# bluetooth_2.net
KiCad netlist of a schematic drawn in Altium Designer
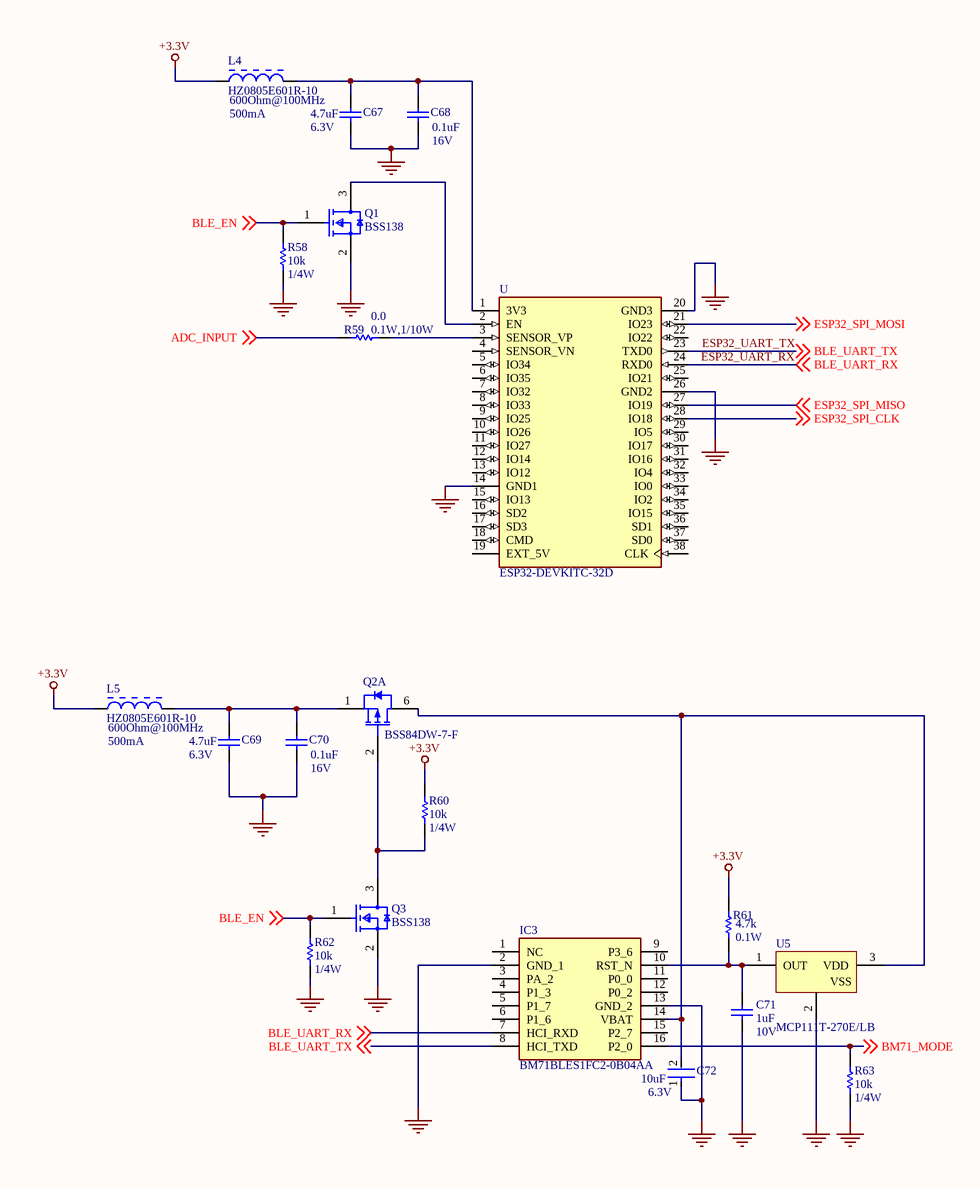
[diagram p0: bluetooth 2.SchDoc]

(export (version "E")
  (design (tool "Eeschema 10.0.6"))
  (components
    (comp (ref "C67")
      (value "4.7uF")
      (footprint "CAPC2013X145X50NL20T25")
      (fields
        (field (name "PART NUMBER") "C0805C475K9PACTU")
        (field (name "MANUFACTURER") "Kemet")
        (field (name "VOLTAGE") "6.3V")
      )
      (libsource (lib "Altium Content Vault") (part "CAP"))
    )
    (comp (ref "C68")
      (value "0.1uF")
      (footprint "CAPC1608X87X35ML15T15")
      (description "Ceramic Capacitor 0.1uF 16V +-10% X7R0603")
      (fields
        (field (name "PART NUMBER") "C0603C104M4RACTU")
        (field (name "MANUFACTURER") "Kemet")
        (field (name "VOLTAGE") "16V")
      )
      (libsource (lib "Altium Content Vault") (part "CAP"))
    )
    (comp (ref "C69")
      (value "4.7uF")
      (footprint "CAPC2013X145X50NL20T25")
      (fields
        (field (name "PART NUMBER") "C0805C475K9PACTU")
        (field (name "MANUFACTURER") "Kemet")
        (field (name "VOLTAGE") "6.3V")
      )
      (libsource (lib "Altium Content Vault") (part "CAP"))
    )
    (comp (ref "C70")
      (value "0.1uF")
      (footprint "CAPC1608X87X35ML15T15")
      (description "Ceramic Capacitor 0.1uF 16V +-10% X7R0603")
      (fields
        (field (name "PART NUMBER") "C0603C104M4RACTU")
        (field (name "MANUFACTURER") "Kemet")
        (field (name "VOLTAGE") "16V")
      )
      (libsource (lib "Altium Content Vault") (part "CAP"))
    )
    (comp (ref "C71")
      (value "1uF")
      (footprint "CAPC1608X90X35ML15T15")
      (fields
        (field (name "MANUFACTURER") "Kemet")
        (field (name "PART NUMBER") "C0603C105K8RACTU")
        (field (name "VOLTAGE") "10V")
      )
      (libsource (lib "Altium Content Vault") (part "CAP"))
    )
    (comp (ref "C72")
      (value "10uF")
      (footprint "FP-CL10-IPC_C")
      (description "Cap Ceramic 10uF 6.3V X5R ±20% Pad SMD 0603 +85°C T/R")
      (fields
        (field (name "VOLTAGE") "6.3V")
        (field (name "TOLERANCE") "20%")
        (field (name "MANUFACTURER") "Samsung")
      )
      (libsource (lib "Altium Content Vault") (part "b4654b650e69147ec39a6b967a45e02"))
    )
    (comp (ref "IC3")
      (value "BM71BLES1FC2-0B04AA")
      (footprint "SamacSys:BM71BLES1FC2_1")
      (description "Integrated Circuit")
      (fields (field (name "MOUSER PART NUMBER") "579-BM71BS1FC2-BB04"))
      (libsource (lib "SamacSys") (part "BM71BLES1FC2-0B04AA"))
    )
    (comp (ref "L4")
      (value "HZ0805E601R-10")
      (footprint "LIRD-LI0805H151R-10-2_V")
      (fields
        (field (name "IMPEDANCE @ FREQUENCY") "600Ohm@100MHz")
        (field (name "MANUFACTURER") "Laird")
        (field (name "CURRENT RATING (MAX)") "500mA")
      )
      (libsource (lib "Altium Content Vault") (part "IND-FB-2"))
    )
    (comp (ref "L5")
      (value "HZ0805E601R-10")
      (footprint "LIRD-LI0805H151R-10-2_V")
      (fields
        (field (name "IMPEDANCE @ FREQUENCY") "600Ohm@100MHz")
        (field (name "MANUFACTURER") "Laird")
        (field (name "CURRENT RATING (MAX)") "500mA")
      )
      (libsource (lib "Altium Content Vault") (part "IND-FB-2"))
    )
    (comp (ref "Q1")
      (value "BSS138")
      (footprint "FP-318-08-IPC_B")
      (description "MOSFET N-CH 50V 220MA SOT-23")
      (libsource (lib "Altium Content Vault") (part "3b9c635fedb024a5347a57b145af9cc"))
    )
    (comp (ref "Q2")
      (value "BSS84DW-7-F")
      (footprint "DIOD-SOT363-6_V")
      (description "Dual P-Channel Enhancement Mode MOSFET, 50 VDS, -55 to 150 degC, 6-Pin SOT363, RoHS, Tape and Reel")
      (fields (field (name "MANUFACTURER") "DiodesIncorporated"))
      (libsource (lib "Altium Content Vault") (part "PEMOS-SGD-SGD-6"))
    )
    (comp (ref "Q3")
      (value "BSS138")
      (footprint "FP-318-08-IPC_B")
      (description "MOSFET N-CH 50V 220MA SOT-23")
      (libsource (lib "Altium Content Vault") (part "3b9c635fedb024a5347a57b145af9cc"))
    )
    (comp (ref "R58")
      (value "10k")
      (footprint "RESC3216X70X50NL05T20")
      (description "Res Thick Film 1206 10k Ohms 5% 1/4W")
      (fields
        (field (name "PART NUMBER") "ERJ-8GEYJ103V")
        (field (name "MANUFACTURER") "Panasonic")
        (field (name "POWER") "1/4W")
      )
      (libsource (lib "Altium Content Vault") (part "RES"))
    )
    (comp (ref "R59")
      (value "0.0")
      (footprint "RESC1608X55X35LL10T10")
      (description "Chip Resistor, 0 Ohm, +/- 5%, 0.1 W, -55 to 155 degC, 0603 (1608 Metric), RoHS, Tape and Reel")
      (fields
        (field (name "POWER") "0.1W,1/10W")
        (field (name "MANUFACTURER") "Samsung-Electro-Mechanics-America,-Inc.")
        (field (name "TOLERANCE") "Jumper")
      )
      (libsource (lib "Altium Content Vault") (part "RES-2"))
    )
    (comp (ref "R60")
      (value "10k")
      (footprint "RESC3216X70X50NL05T20")
      (description "Res Thick Film 1206 10k Ohms 5% 1/4W")
      (fields
        (field (name "PART NUMBER") "ERJ-8GEYJ103V")
        (field (name "MANUFACTURER") "Panasonic")
        (field (name "POWER") "1/4W")
      )
      (libsource (lib "Altium Content Vault") (part "RES"))
    )
    (comp (ref "R61")
      (value "4.7k")
      (footprint "RESC1608X55X25LL10T15")
      (description "Chip Resistor, 4.7 KOhm, +/- 1%, 0.1 W, -55 to 155 degC, 0603 (1608 Metric), RoHS, Tape and Reel")
      (fields
        (field (name "POWER") "0.1W")
        (field (name "MANUFACTURER") "Yageo")
        (field (name "TOLERANCE") "1%")
      )
      (libsource (lib "Altium Content Vault") (part "RES-2"))
    )
    (comp (ref "R62")
      (value "10k")
      (footprint "RESC3216X70X50NL05T20")
      (description "Res Thick Film 1206 10k Ohms 5% 1/4W")
      (fields
        (field (name "PART NUMBER") "ERJ-8GEYJ103V")
        (field (name "MANUFACTURER") "Panasonic")
        (field (name "POWER") "1/4W")
      )
      (libsource (lib "Altium Content Vault") (part "RES"))
    )
    (comp (ref "R63")
      (value "10k")
      (footprint "RESC3216X70X50NL05T20")
      (description "Res Thick Film 1206 10k Ohms 5% 1/4W")
      (fields
        (field (name "PART NUMBER") "ERJ-8GEYJ103V")
        (field (name "MANUFACTURER") "Panasonic")
        (field (name "POWER") "1/4W")
      )
      (libsource (lib "Altium Content Vault") (part "RES"))
    )
    (comp (ref "U")
      (value "ESP32-DEVKITC-32D")
      (footprint "MODULE_ESP32-DEVKITC-32D")
      (fields (field (name "MF") "Espressif Systems"))
      (libsource (lib "ESP32-DEVKITC-32D") (part "ESP32-DEVKITC-32D"))
    )
    (comp (ref "U5")
      (value "MCP111T-270E/LB")
      (footprint "SC70-LB3_N")
      (libsource (lib "Altium Content Vault") (part "PM-VLTD-MCP11X-SOT3"))
    )
  )
  (nets
    (net (code "1") (name "+3.3V") (class "Default")
      (node (ref "L4") (pin "1") (pinfunction "1_1") (pintype "passive"))
      (node (ref "L5") (pin "1") (pinfunction "1_1") (pintype "passive"))
      (node (ref "R60") (pin "1") (pinfunction "1_1") (pintype "passive"))
      (node (ref "R61") (pin "2") (pinfunction "2_2") (pintype "passive"))
    )
    (net (code "2") (name "ADC_INPUT") (class "Default")
      (node (ref "R59") (pin "1") (pinfunction "1_1") (pintype "passive"))
    )
    (net (code "3") (name "BLE_EN") (class "Default")
      (node (ref "Q1") (pin "1") (pinfunction "G_1") (pintype "passive"))
      (node (ref "Q3") (pin "1") (pinfunction "G_1") (pintype "passive"))
      (node (ref "R58") (pin "1") (pinfunction "1_1") (pintype "passive"))
      (node (ref "R62") (pin "1") (pinfunction "1_1") (pintype "passive"))
    )
    (net (code "4") (name "BLE_UART_RX") (class "Default")
      (node (ref "IC3") (pin "7") (pinfunction "HCI_RXD_7") (pintype "passive"))
      (node (ref "U") (pin "24") (pinfunction "RXD0_24") (pintype "input"))
    )
    (net (code "5") (name "BLE_UART_TX") (class "Default")
      (node (ref "IC3") (pin "8") (pinfunction "HCI_TXD_8") (pintype "passive"))
      (node (ref "U") (pin "23") (pinfunction "TXD0_23") (pintype "output"))
    )
    (net (code "6") (name "BM71_MODE") (class "Default")
      (node (ref "IC3") (pin "16") (pinfunction "P2_0_16") (pintype "passive"))
      (node (ref "R63") (pin "1") (pinfunction "1_1") (pintype "passive"))
    )
    (net (code "7") (name "ESP32_SPI_CLK") (class "Default")
      (node (ref "U") (pin "28") (pinfunction "IO18_28") (pintype "bidirectional"))
    )
    (net (code "8") (name "ESP32_SPI_MISO") (class "Default")
      (node (ref "U") (pin "27") (pinfunction "IO19_27") (pintype "bidirectional"))
    )
    (net (code "9") (name "ESP32_SPI_MOSI") (class "Default")
      (node (ref "U") (pin "21") (pinfunction "IO23_21") (pintype "bidirectional"))
    )
    (net (code "10") (name "GND") (class "Default")
      (node (ref "C67") (pin "1") (pinfunction "1_1") (pintype "passive"))
      (node (ref "C68") (pin "1") (pinfunction "1_1") (pintype "passive"))
      (node (ref "C69") (pin "1") (pinfunction "1_1") (pintype "passive"))
      (node (ref "C70") (pin "1") (pinfunction "1_1") (pintype "passive"))
      (node (ref "C71") (pin "1") (pinfunction "1_1") (pintype "passive"))
      (node (ref "C72") (pin "1") (pinfunction "1_1") (pintype "passive"))
      (node (ref "IC3") (pin "13") (pinfunction "GND_2_13") (pintype "passive"))
      (node (ref "IC3") (pin "2") (pinfunction "GND_1_2") (pintype "passive"))
      (node (ref "Q1") (pin "2") (pinfunction "S_2") (pintype "passive"))
      (node (ref "Q3") (pin "2") (pinfunction "S_2") (pintype "passive"))
      (node (ref "R58") (pin "2") (pinfunction "2_2") (pintype "passive"))
      (node (ref "R62") (pin "2") (pinfunction "2_2") (pintype "passive"))
      (node (ref "R63") (pin "2") (pinfunction "2_2") (pintype "passive"))
      (node (ref "U") (pin "14") (pinfunction "GND1_14") (pintype "power_in"))
      (node (ref "U") (pin "20") (pinfunction "GND3_20") (pintype "power_in"))
      (node (ref "U") (pin "26") (pinfunction "GND2_26") (pintype "power_in"))
      (node (ref "U5") (pin "2") (pinfunction "VSS_2") (pintype "power_in"))
    )
    (net (code "11") (name "Net-(IC3-RST_N)") (class "Default")
      (node (ref "C71") (pin "2") (pinfunction "2_2") (pintype "passive"))
      (node (ref "IC3") (pin "10") (pinfunction "RST_N_10") (pintype "passive"))
      (node (ref "R61") (pin "1") (pinfunction "1_1") (pintype "passive"))
      (node (ref "U5") (pin "1") (pinfunction "OUT_1") (pintype "power_in"))
    )
    (net (code "12") (name "Net-(IC3-VBAT)") (class "Default")
      (node (ref "C72") (pin "2") (pinfunction "2_2") (pintype "passive"))
      (node (ref "IC3") (pin "14") (pinfunction "VBAT_14") (pintype "passive"))
      (node (ref "Q2") (pin "6") (pinfunction "D_6") (pintype "passive"))
      (node (ref "U5") (pin "3") (pinfunction "VDD_3") (pintype "power_in"))
    )
    (net (code "13") (name "Net-(Q1-D)") (class "Default")
      (node (ref "Q1") (pin "3") (pinfunction "D_3") (pintype "passive"))
      (node (ref "U") (pin "2") (pinfunction "EN_2") (pintype "input"))
    )
    (net (code "14") (name "Net-(Q2A-G)") (class "Default")
      (node (ref "Q2") (pin "2") (pinfunction "G_2") (pintype "passive"))
      (node (ref "Q3") (pin "3") (pinfunction "D_3") (pintype "passive"))
      (node (ref "R60") (pin "2") (pinfunction "2_2") (pintype "passive"))
    )
    (net (code "15") (name "Net-(Q2A-S)") (class "Default")
      (node (ref "C69") (pin "2") (pinfunction "2_2") (pintype "passive"))
      (node (ref "C70") (pin "2") (pinfunction "2_2") (pintype "passive"))
      (node (ref "L5") (pin "2") (pinfunction "2_2") (pintype "passive"))
      (node (ref "Q2") (pin "1") (pinfunction "S_1") (pintype "passive"))
    )
    (net (code "16") (name "Net-(U-3V3)") (class "Default")
      (node (ref "C67") (pin "2") (pinfunction "2_2") (pintype "passive"))
      (node (ref "C68") (pin "2") (pinfunction "2_2") (pintype "passive"))
      (node (ref "L4") (pin "2") (pinfunction "2_2") (pintype "passive"))
      (node (ref "U") (pin "1") (pinfunction "3V3_1") (pintype "power_in"))
    )
    (net (code "17") (name "Net-(U-SENSOR_VP)") (class "Default")
      (node (ref "R59") (pin "2") (pinfunction "2_2") (pintype "passive"))
      (node (ref "U") (pin "3") (pinfunction "SENSOR_VP_3") (pintype "input"))
    )
    (net (code "18") (name "unconnected-(IC3-NC-Pad1)") (class "Default")
      (node (ref "IC3") (pin "1") (pinfunction "NC_1") (pintype "passive"))
    )
    (net (code "19") (name "unconnected-(IC3-P0_0-Pad11)") (class "Default")
      (node (ref "IC3") (pin "11") (pinfunction "P0_0_11") (pintype "passive"))
    )
    (net (code "20") (name "unconnected-(IC3-P0_2-Pad12)") (class "Default")
      (node (ref "IC3") (pin "12") (pinfunction "P0_2_12") (pintype "passive"))
    )
    (net (code "21") (name "unconnected-(IC3-P1_3-Pad4)") (class "Default")
      (node (ref "IC3") (pin "4") (pinfunction "P1_3_4") (pintype "passive"))
    )
    (net (code "22") (name "unconnected-(IC3-P1_6-Pad6)") (class "Default")
      (node (ref "IC3") (pin "6") (pinfunction "P1_6_6") (pintype "passive"))
    )
    (net (code "23") (name "unconnected-(IC3-P1_7-Pad5)") (class "Default")
      (node (ref "IC3") (pin "5") (pinfunction "P1_7_5") (pintype "passive"))
    )
    (net (code "24") (name "unconnected-(IC3-P2_7-Pad15)") (class "Default")
      (node (ref "IC3") (pin "15") (pinfunction "P2_7_15") (pintype "passive"))
    )
    (net (code "25") (name "unconnected-(IC3-P3_6-Pad9)") (class "Default")
      (node (ref "IC3") (pin "9") (pinfunction "P3_6_9") (pintype "passive"))
    )
    (net (code "26") (name "unconnected-(IC3-PA_2-Pad3)") (class "Default")
      (node (ref "IC3") (pin "3") (pinfunction "PA_2_3") (pintype "passive"))
    )
    (net (code "27") (name "unconnected-(U-CLK-Pad38)") (class "Default")
      (node (ref "U") (pin "38") (pinfunction "CLK_38") (pintype "input"))
    )
    (net (code "28") (name "unconnected-(U-CMD-Pad18)") (class "Default")
      (node (ref "U") (pin "18") (pinfunction "CMD_18") (pintype "bidirectional"))
    )
    (net (code "29") (name "unconnected-(U-EXT_5V-Pad19)") (class "Default")
      (node (ref "U") (pin "19") (pinfunction "EXT_5V_19") (pintype "power_in"))
    )
    (net (code "30") (name "unconnected-(U-IO0-Pad33)") (class "Default")
      (node (ref "U") (pin "33") (pinfunction "IO0_33") (pintype "bidirectional"))
    )
    (net (code "31") (name "unconnected-(U-IO2-Pad34)") (class "Default")
      (node (ref "U") (pin "34") (pinfunction "IO2_34") (pintype "bidirectional"))
    )
    (net (code "32") (name "unconnected-(U-IO4-Pad32)") (class "Default")
      (node (ref "U") (pin "32") (pinfunction "IO4_32") (pintype "bidirectional"))
    )
    (net (code "33") (name "unconnected-(U-IO5-Pad29)") (class "Default")
      (node (ref "U") (pin "29") (pinfunction "IO5_29") (pintype "bidirectional"))
    )
    (net (code "34") (name "unconnected-(U-IO12-Pad13)") (class "Default")
      (node (ref "U") (pin "13") (pinfunction "IO12_13") (pintype "bidirectional"))
    )
    (net (code "35") (name "unconnected-(U-IO13-Pad15)") (class "Default")
      (node (ref "U") (pin "15") (pinfunction "IO13_15") (pintype "bidirectional"))
    )
    (net (code "36") (name "unconnected-(U-IO14-Pad12)") (class "Default")
      (node (ref "U") (pin "12") (pinfunction "IO14_12") (pintype "bidirectional"))
    )
    (net (code "37") (name "unconnected-(U-IO15-Pad35)") (class "Default")
      (node (ref "U") (pin "35") (pinfunction "IO15_35") (pintype "bidirectional"))
    )
    (net (code "38") (name "unconnected-(U-IO16-Pad31)") (class "Default")
      (node (ref "U") (pin "31") (pinfunction "IO16_31") (pintype "bidirectional"))
    )
    (net (code "39") (name "unconnected-(U-IO17-Pad30)") (class "Default")
      (node (ref "U") (pin "30") (pinfunction "IO17_30") (pintype "bidirectional"))
    )
    (net (code "40") (name "unconnected-(U-IO21-Pad25)") (class "Default")
      (node (ref "U") (pin "25") (pinfunction "IO21_25") (pintype "bidirectional"))
    )
    (net (code "41") (name "unconnected-(U-IO22-Pad22)") (class "Default")
      (node (ref "U") (pin "22") (pinfunction "IO22_22") (pintype "bidirectional"))
    )
    (net (code "42") (name "unconnected-(U-IO25-Pad9)") (class "Default")
      (node (ref "U") (pin "9") (pinfunction "IO25_9") (pintype "bidirectional"))
    )
    (net (code "43") (name "unconnected-(U-IO26-Pad10)") (class "Default")
      (node (ref "U") (pin "10") (pinfunction "IO26_10") (pintype "bidirectional"))
    )
    (net (code "44") (name "unconnected-(U-IO27-Pad11)") (class "Default")
      (node (ref "U") (pin "11") (pinfunction "IO27_11") (pintype "bidirectional"))
    )
    (net (code "45") (name "unconnected-(U-IO32-Pad7)") (class "Default")
      (node (ref "U") (pin "7") (pinfunction "IO32_7") (pintype "bidirectional"))
    )
    (net (code "46") (name "unconnected-(U-IO33-Pad8)") (class "Default")
      (node (ref "U") (pin "8") (pinfunction "IO33_8") (pintype "bidirectional"))
    )
    (net (code "47") (name "unconnected-(U-IO34-Pad5)") (class "Default")
      (node (ref "U") (pin "5") (pinfunction "IO34_5") (pintype "bidirectional"))
    )
    (net (code "48") (name "unconnected-(U-IO35-Pad6)") (class "Default")
      (node (ref "U") (pin "6") (pinfunction "IO35_6") (pintype "bidirectional"))
    )
    (net (code "49") (name "unconnected-(U-SD0-Pad37)") (class "Default")
      (node (ref "U") (pin "37") (pinfunction "SD0_37") (pintype "bidirectional"))
    )
    (net (code "50") (name "unconnected-(U-SD1-Pad36)") (class "Default")
      (node (ref "U") (pin "36") (pinfunction "SD1_36") (pintype "bidirectional"))
    )
    (net (code "51") (name "unconnected-(U-SD2-Pad16)") (class "Default")
      (node (ref "U") (pin "16") (pinfunction "SD2_16") (pintype "bidirectional"))
    )
    (net (code "52") (name "unconnected-(U-SD3-Pad17)") (class "Default")
      (node (ref "U") (pin "17") (pinfunction "SD3_17") (pintype "bidirectional"))
    )
    (net (code "53") (name "unconnected-(U-SENSOR_VN-Pad4)") (class "Default")
      (node (ref "U") (pin "4") (pinfunction "SENSOR_VN_4") (pintype "input"))
    )
  )
)
